# BS5T2MBoard.net
KiCad netlist of a schematic drawn in Altium Designer
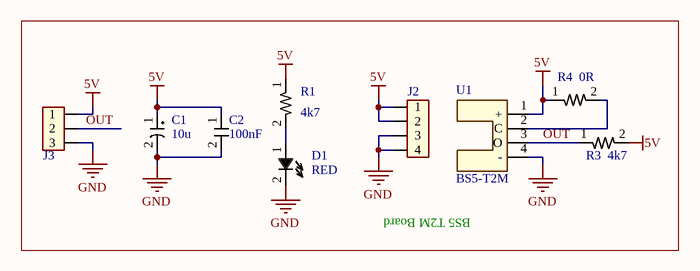
[diagram p0: BS5T2MBoard.SchDoc]

(export (version "E")
  (design (tool "Eeschema 10.0.6"))
  (components
    (comp (ref "C1")
      (value "10u")
      (footprint "HieuAltiLib:Tantalum Size A")
      (description "Polarised Capacitor")
      (fields (field (name "Comment") "Cap Pol"))
      (libsource (lib "HieuAltiLib") (part "Cap Pol"))
    )
    (comp (ref "C2")
      (value "100nF")
      (footprint "HieuAltiLib:C0805")
      (description "Non Polarised Capacitor")
      (fields (field (name "Comment") "Cap Non Pol"))
      (libsource (lib "HieuAltiLib") (part "Cap Non Pol"))
    )
    (comp (ref "D1")
      (value "RED")
      (footprint "HieuAltiLib:D0805")
      (description "LED")
      (libsource (lib "HieuAltiLib") (part "LED"))
    )
    (comp (ref "J2")
      (value "Header 1x4")
      (footprint "HieuAltiLib:Header 1x4 Oval")
      (description "2.54mm Single Male/Female Pin Header")
      (libsource (lib "HieuAltiLib") (part "Header 1x4"))
    )
    (comp (ref "J3")
      (value "Header 1x3")
      (footprint "HieuAltiLib:Header 1x3 Oval")
      (description "2.54mm Single Male/Female Pin Header")
      (libsource (lib "HieuAltiLib") (part "Header 1x3"))
    )
    (comp (ref "R1")
      (value "4k7")
      (footprint "HieuAltiLib:R0805")
      (description "Resistor")
      (libsource (lib "HieuAltiLib") (part "Resistor"))
    )
    (comp (ref "R3")
      (value "4k7")
      (footprint "HieuAltiLib:R0805")
      (description "Resistor")
      (libsource (lib "") (part "Resistor_1"))
    )
    (comp (ref "R4")
      (value "0R")
      (footprint "HieuAltiLib:R0805")
      (description "Resistor")
      (libsource (lib "") (part "Resistor_1"))
    )
    (comp (ref "U1")
      (value "BS5-T2M")
      (footprint "HieuAltiLib:BS5-T2M")
      (description "Opto Interrupter, Sensing Distance 5mm")
      (libsource (lib "HieuAltiLib") (part "BS5-T2M"))
    )
  )
  (nets
    (net (code "1") (name "/OUT") (class "Default")
      (node (ref "J3") (pin "2") (pinfunction "2_2") (pintype "passive"))
      (node (ref "R3") (pin "1") (pintype "passive"))
      (node (ref "U1") (pin "3") (pinfunction "O_3") (pintype "passive"))
    )
    (net (code "2") (name "5V") (class "Default")
      (node (ref "C1") (pin "1") (pintype "passive"))
      (node (ref "C2") (pin "1") (pintype "passive"))
      (node (ref "J2") (pin "1") (pinfunction "1_1") (pintype "passive"))
      (node (ref "J2") (pin "2") (pinfunction "2_2") (pintype "passive"))
      (node (ref "J3") (pin "1") (pinfunction "1_1") (pintype "passive"))
      (node (ref "R1") (pin "1") (pintype "passive"))
      (node (ref "R3") (pin "2") (pintype "passive"))
      (node (ref "R4") (pin "1") (pintype "passive"))
      (node (ref "U1") (pin "1") (pinfunction "+_1") (pintype "passive"))
    )
    (net (code "3") (name "GND") (class "Default")
      (node (ref "C1") (pin "2") (pintype "passive"))
      (node (ref "C2") (pin "2") (pintype "passive"))
      (node (ref "D1") (pin "2") (pintype "passive"))
      (node (ref "J2") (pin "3") (pinfunction "3_3") (pintype "passive"))
      (node (ref "J2") (pin "4") (pinfunction "4_4") (pintype "passive"))
      (node (ref "J3") (pin "3") (pinfunction "3_3") (pintype "passive"))
      (node (ref "U1") (pin "4") (pinfunction "-_4") (pintype "passive"))
    )
    (net (code "4") (name "Net-(D1-Pad1)") (class "Default")
      (node (ref "D1") (pin "1") (pintype "passive"))
      (node (ref "R1") (pin "2") (pintype "passive"))
    )
    (net (code "5") (name "Net-(U1-C)") (class "Default")
      (node (ref "R4") (pin "2") (pintype "passive"))
      (node (ref "U1") (pin "2") (pinfunction "C_2") (pintype "passive"))
    )
  )
)
